# SCH_555-Circuit_2025-03-12.net
KiCad netlist of a schematic drawn in EasyEDA
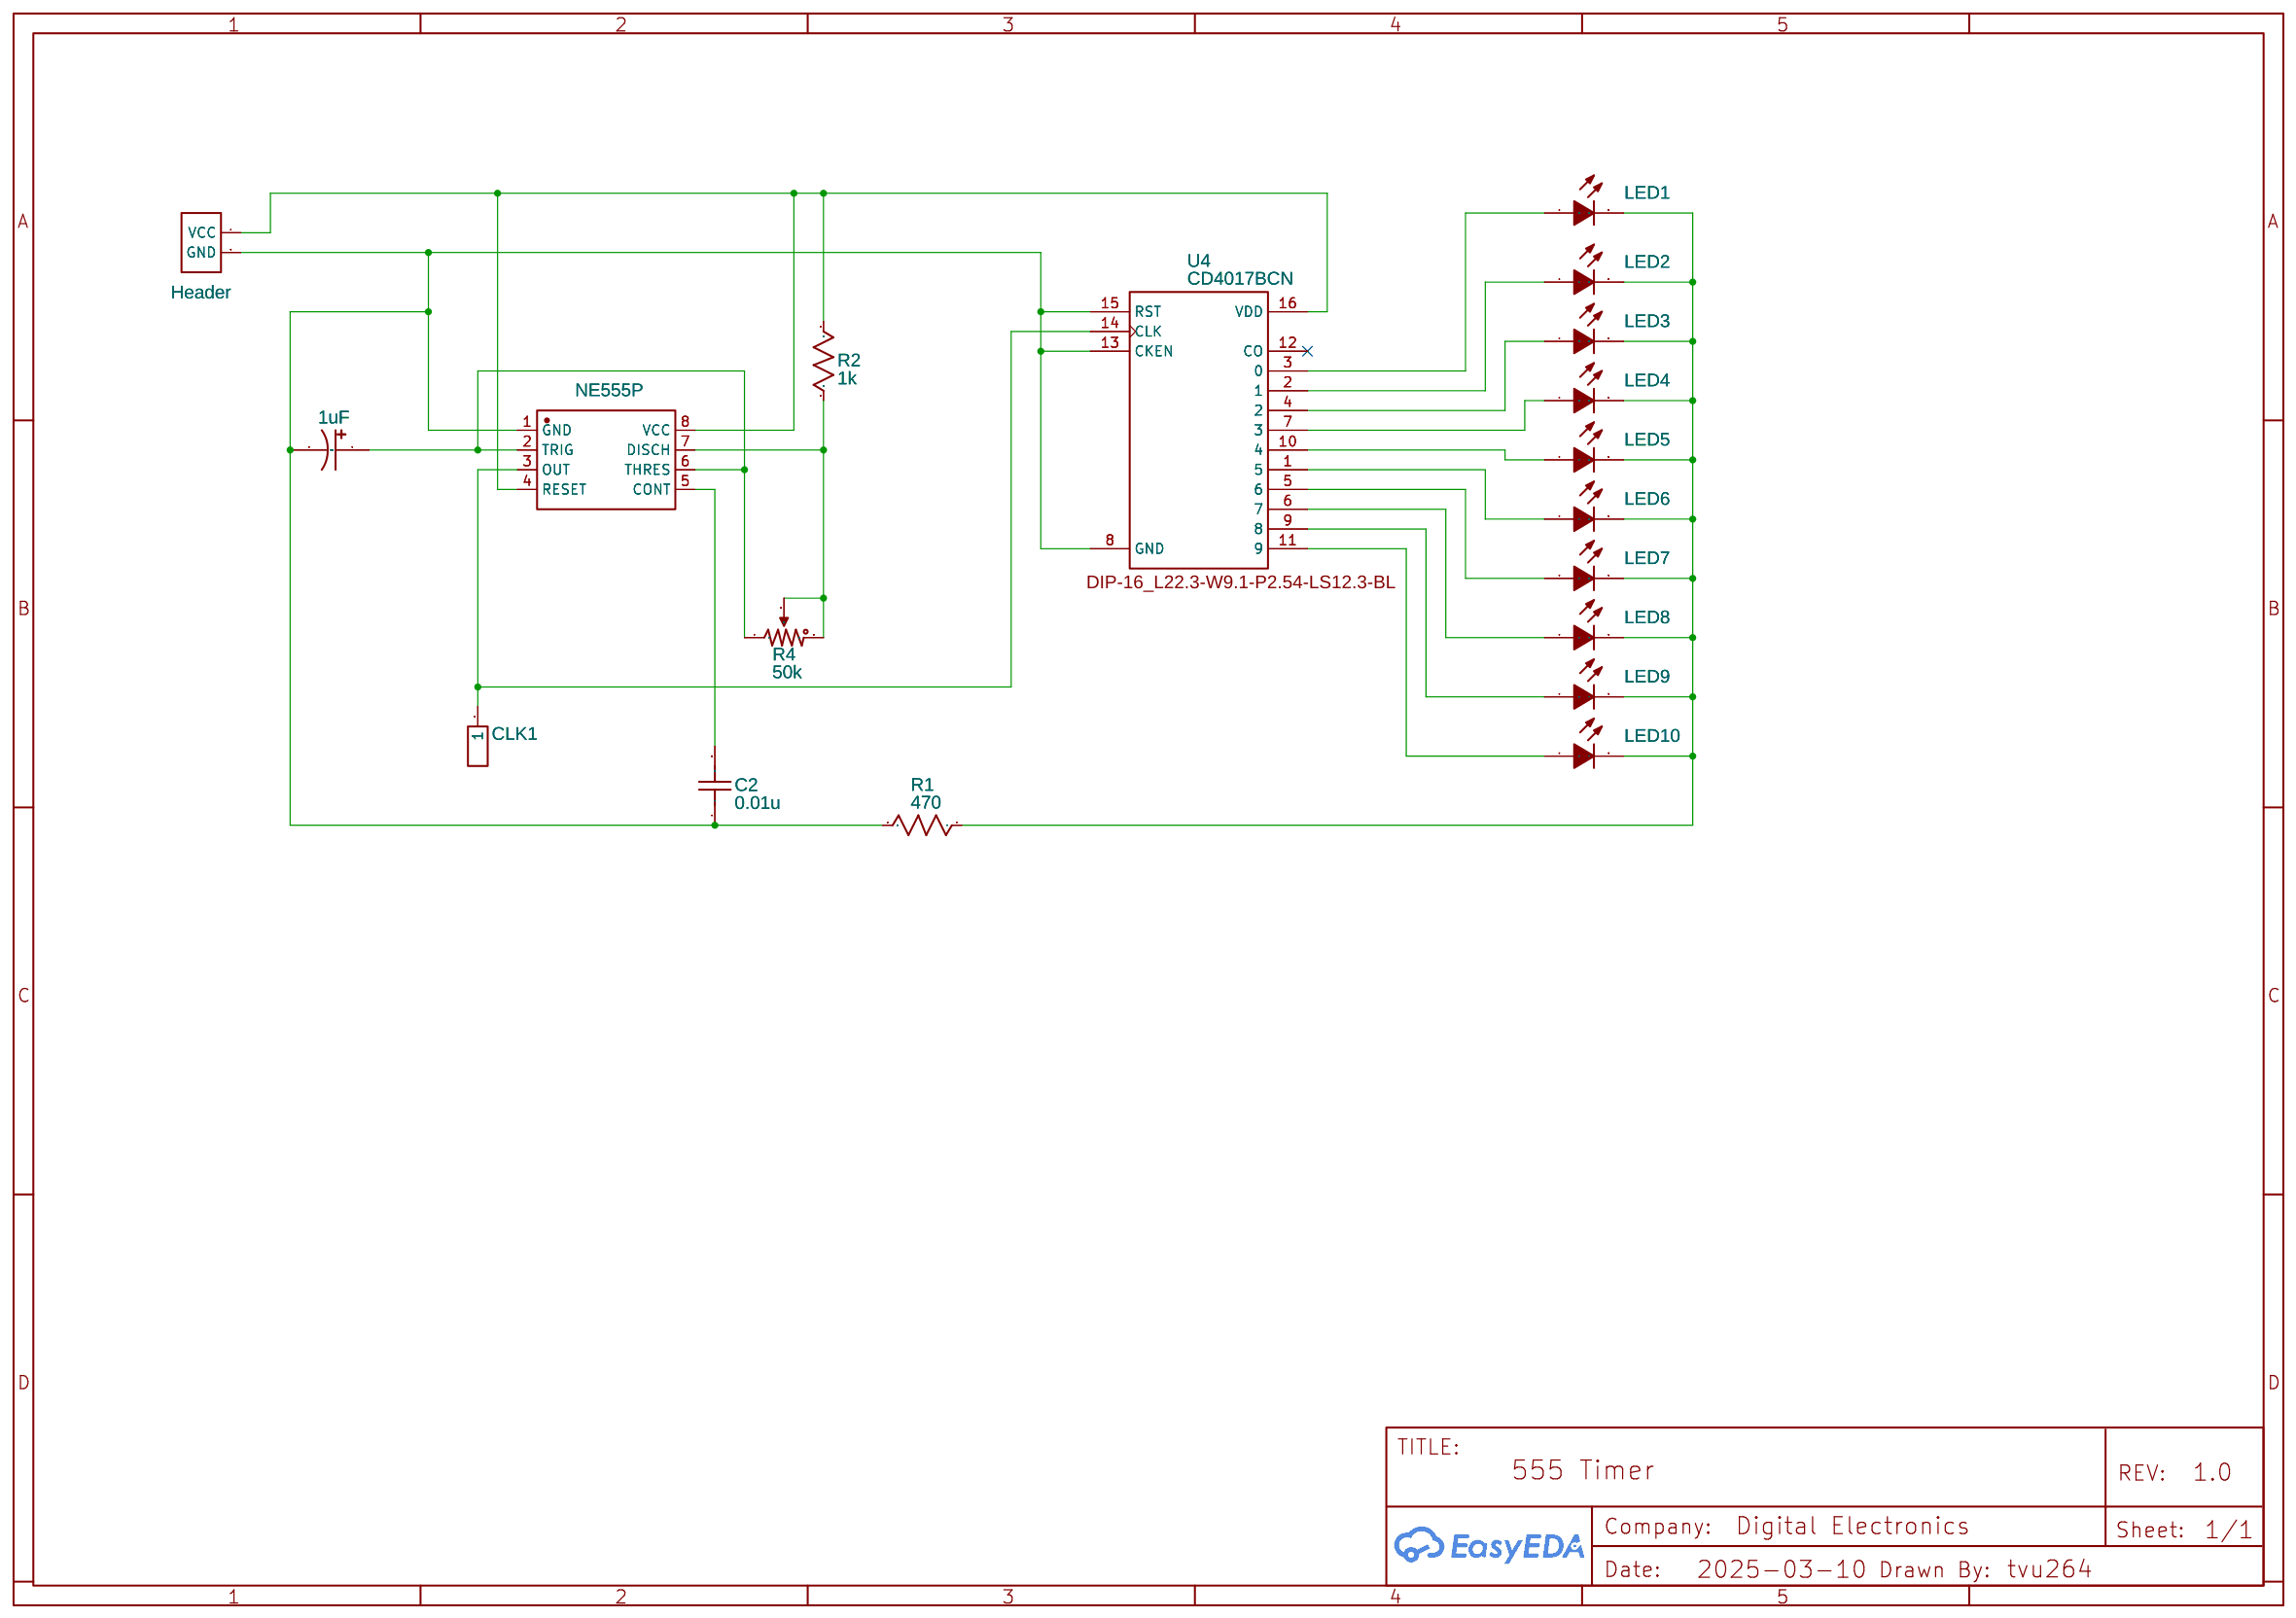
[diagram p0: schematic sheet]

(export (version "E")
  (design (tool "Eeschema 10.0.6"))
  (components
    (comp (ref "C1")
      (value "1uF")
      (fields (field (name "Manufacturer Part") "UVZ1H010MDD") (field (name "Manufacturer") "Nichicon(尼吉康)"))
      (libsource (lib "") (part "UVZ1H010MDD"))
    )
    (comp (ref "C2") (value "0.01u") (libsource (lib "") (part "C_0603_US")))
    (comp (ref "CLK1")
      (value "C81276")
      (fields
        (field (name "Manufacturer Part") "2.54-1*1P针")
        (field (name "Manufacturer") "BOOMELE(Boom Precision Elec)")
      )
      (libsource (lib "") (part "Header-Male-2.54_1x1"))
    )
    (comp (ref "H1") (value "Header") (libsource (lib "") (part "HEADER-FEMALE-2.54_1X2")))
    (comp (ref "LED1") (value "LED_5MM") (libsource (lib "") (part "LED_5MM")))
    (comp (ref "LED2") (value "LED_5MM") (libsource (lib "") (part "LED_5MM")))
    (comp (ref "LED3") (value "LED_5MM") (libsource (lib "") (part "LED_5MM")))
    (comp (ref "LED4") (value "LED_5MM") (libsource (lib "") (part "LED_5MM")))
    (comp (ref "LED5") (value "LED_5MM") (libsource (lib "") (part "LED_5MM")))
    (comp (ref "LED6") (value "LED_5MM") (libsource (lib "") (part "LED_5MM")))
    (comp (ref "LED7") (value "LED_5MM") (libsource (lib "") (part "LED_5MM")))
    (comp (ref "LED8") (value "LED_5MM") (libsource (lib "") (part "LED_5MM")))
    (comp (ref "LED9") (value "LED_5MM") (libsource (lib "") (part "LED_5MM")))
    (comp (ref "LED10") (value "LED_5MM") (libsource (lib "") (part "LED_5MM")))
    (comp (ref "R1")
      (value "470")
      (fields (field (name "Manufacturer Part") "?"))
      (libsource (lib "") (part "Resistor"))
    )
    (comp (ref "R2")
      (value "1k")
      (fields (field (name "Manufacturer Part") "?"))
      (libsource (lib "") (part "Resistor_1"))
    )
    (comp (ref "R4")
      (value "50k")
      (fields (field (name "Manufacturer Part") "?"))
      (libsource (lib "") (part "Potentiometer"))
    )
    (comp (ref "U2")
      (value "NE555P")
      (fields (field (name "Manufacturer") "TI(德州仪器)"))
      (libsource (lib "") (part "NE555P"))
    )
    (comp (ref "U4") (value "CD4017BCN") (libsource (lib "") (part "CD4017BCN")))
  )
  (nets
    (net (code "1") (name "Net-(H1-GND)") (class "Default")
      (node (ref "C1") (pin "2") (pinfunction "2_2") (pintype "unspecified"))
      (node (ref "C2") (pin "1") (pinfunction "1_1") (pintype "unspecified"))
      (node (ref "H1") (pin "2") (pinfunction "GND_2") (pintype "unspecified"))
      (node (ref "R1") (pin "2") (pinfunction "2_2") (pintype "unspecified"))
      (node (ref "U2") (pin "1") (pinfunction "GND_1") (pintype "unspecified"))
      (node (ref "U4") (pin "13") (pinfunction "CKEN_13") (pintype "unspecified"))
      (node (ref "U4") (pin "15") (pinfunction "RST_15") (pintype "unspecified"))
      (node (ref "U4") (pin "8") (pinfunction "GND_8") (pintype "passive"))
    )
    (net (code "2") (name "Net-(H1-VCC)") (class "Default")
      (node (ref "H1") (pin "1") (pinfunction "VCC_1") (pintype "unspecified"))
      (node (ref "R2") (pin "2") (pinfunction "2_2") (pintype "unspecified"))
      (node (ref "U2") (pin "4") (pinfunction "RESET_4") (pintype "unspecified"))
      (node (ref "U2") (pin "8") (pinfunction "VCC_8") (pintype "unspecified"))
      (node (ref "U4") (pin "16") (pinfunction "VDD_16") (pintype "passive"))
    )
    (net (code "3") (name "Net-(LED1-A)") (class "Default")
      (node (ref "LED1") (pin "1") (pinfunction "A_1") (pintype "input"))
      (node (ref "U4") (pin "3") (pinfunction "0_3") (pintype "output"))
    )
    (net (code "4") (name "Net-(LED1-K)") (class "Default")
      (node (ref "LED1") (pin "2") (pinfunction "K_2") (pintype "input"))
      (node (ref "LED10") (pin "2") (pinfunction "K_2") (pintype "input"))
      (node (ref "LED2") (pin "2") (pinfunction "K_2") (pintype "input"))
      (node (ref "LED3") (pin "2") (pinfunction "K_2") (pintype "input"))
      (node (ref "LED4") (pin "2") (pinfunction "K_2") (pintype "input"))
      (node (ref "LED5") (pin "2") (pinfunction "K_2") (pintype "input"))
      (node (ref "LED6") (pin "2") (pinfunction "K_2") (pintype "input"))
      (node (ref "LED7") (pin "2") (pinfunction "K_2") (pintype "input"))
      (node (ref "LED8") (pin "2") (pinfunction "K_2") (pintype "input"))
      (node (ref "LED9") (pin "2") (pinfunction "K_2") (pintype "input"))
      (node (ref "R1") (pin "1") (pinfunction "1_1") (pintype "unspecified"))
    )
    (net (code "5") (name "Net-(LED2-A)") (class "Default")
      (node (ref "LED2") (pin "1") (pinfunction "A_1") (pintype "input"))
      (node (ref "U4") (pin "2") (pinfunction "1_2") (pintype "output"))
    )
    (net (code "6") (name "Net-(LED3-A)") (class "Default")
      (node (ref "LED3") (pin "1") (pinfunction "A_1") (pintype "input"))
      (node (ref "U4") (pin "4") (pinfunction "2_4") (pintype "output"))
    )
    (net (code "7") (name "Net-(LED4-A)") (class "Default")
      (node (ref "LED4") (pin "1") (pinfunction "A_1") (pintype "input"))
      (node (ref "U4") (pin "7") (pinfunction "3_7") (pintype "output"))
    )
    (net (code "8") (name "Net-(LED5-A)") (class "Default")
      (node (ref "LED5") (pin "1") (pinfunction "A_1") (pintype "input"))
      (node (ref "U4") (pin "10") (pinfunction "4_10") (pintype "output"))
    )
    (net (code "9") (name "Net-(LED6-A)") (class "Default")
      (node (ref "LED6") (pin "1") (pinfunction "A_1") (pintype "input"))
      (node (ref "U4") (pin "1") (pinfunction "5_1") (pintype "output"))
    )
    (net (code "10") (name "Net-(LED7-A)") (class "Default")
      (node (ref "LED7") (pin "1") (pinfunction "A_1") (pintype "input"))
      (node (ref "U4") (pin "5") (pinfunction "6_5") (pintype "output"))
    )
    (net (code "11") (name "Net-(LED8-A)") (class "Default")
      (node (ref "LED8") (pin "1") (pinfunction "A_1") (pintype "input"))
      (node (ref "U4") (pin "6") (pinfunction "7_6") (pintype "output"))
    )
    (net (code "12") (name "Net-(LED9-A)") (class "Default")
      (node (ref "LED9") (pin "1") (pinfunction "A_1") (pintype "input"))
      (node (ref "U4") (pin "9") (pinfunction "8_9") (pintype "output"))
    )
    (net (code "13") (name "Net-(LED10-A)") (class "Default")
      (node (ref "LED10") (pin "1") (pinfunction "A_1") (pintype "input"))
      (node (ref "U4") (pin "11") (pinfunction "9_11") (pintype "output"))
    )
    (net (code "14") (name "Net-(R4-2)") (class "Default")
      (node (ref "R2") (pin "1") (pinfunction "1_1") (pintype "unspecified"))
      (node (ref "R4") (pin "2") (pinfunction "3_2") (pintype "unspecified"))
      (node (ref "R4") (pin "3") (pinfunction "2_3") (pintype "unspecified"))
      (node (ref "U2") (pin "7") (pinfunction "DISCH_7") (pintype "unspecified"))
    )
    (net (code "15") (name "Net-(U2-CONT)") (class "Default")
      (node (ref "C2") (pin "2") (pinfunction "2_2") (pintype "unspecified"))
      (node (ref "U2") (pin "5") (pinfunction "CONT_5") (pintype "unspecified"))
    )
    (net (code "16") (name "Net-(U2-OUT)") (class "Default")
      (node (ref "CLK1") (pin "1") (pinfunction "1_1") (pintype "unspecified"))
      (node (ref "U2") (pin "3") (pinfunction "OUT_3") (pintype "unspecified"))
      (node (ref "U4") (pin "14") (pinfunction "CLK_14") (pintype "unspecified"))
    )
    (net (code "17") (name "Net-(U2-THRES)") (class "Default")
      (node (ref "C1") (pin "1") (pinfunction "1_1") (pintype "unspecified"))
      (node (ref "R4") (pin "1") (pinfunction "1_1") (pintype "unspecified"))
      (node (ref "U2") (pin "2") (pinfunction "TRIG_2") (pintype "unspecified"))
      (node (ref "U2") (pin "6") (pinfunction "THRES_6") (pintype "unspecified"))
    )
    (net (code "18") (name "unconnected-(U4-CO-Pad12)") (class "Default")
      (node (ref "U4") (pin "12") (pinfunction "CO_12") (pintype "output+no_connect"))
    )
  )
)
